# surface.net
KiCad netlist of a schematic drawn in Altium Designer
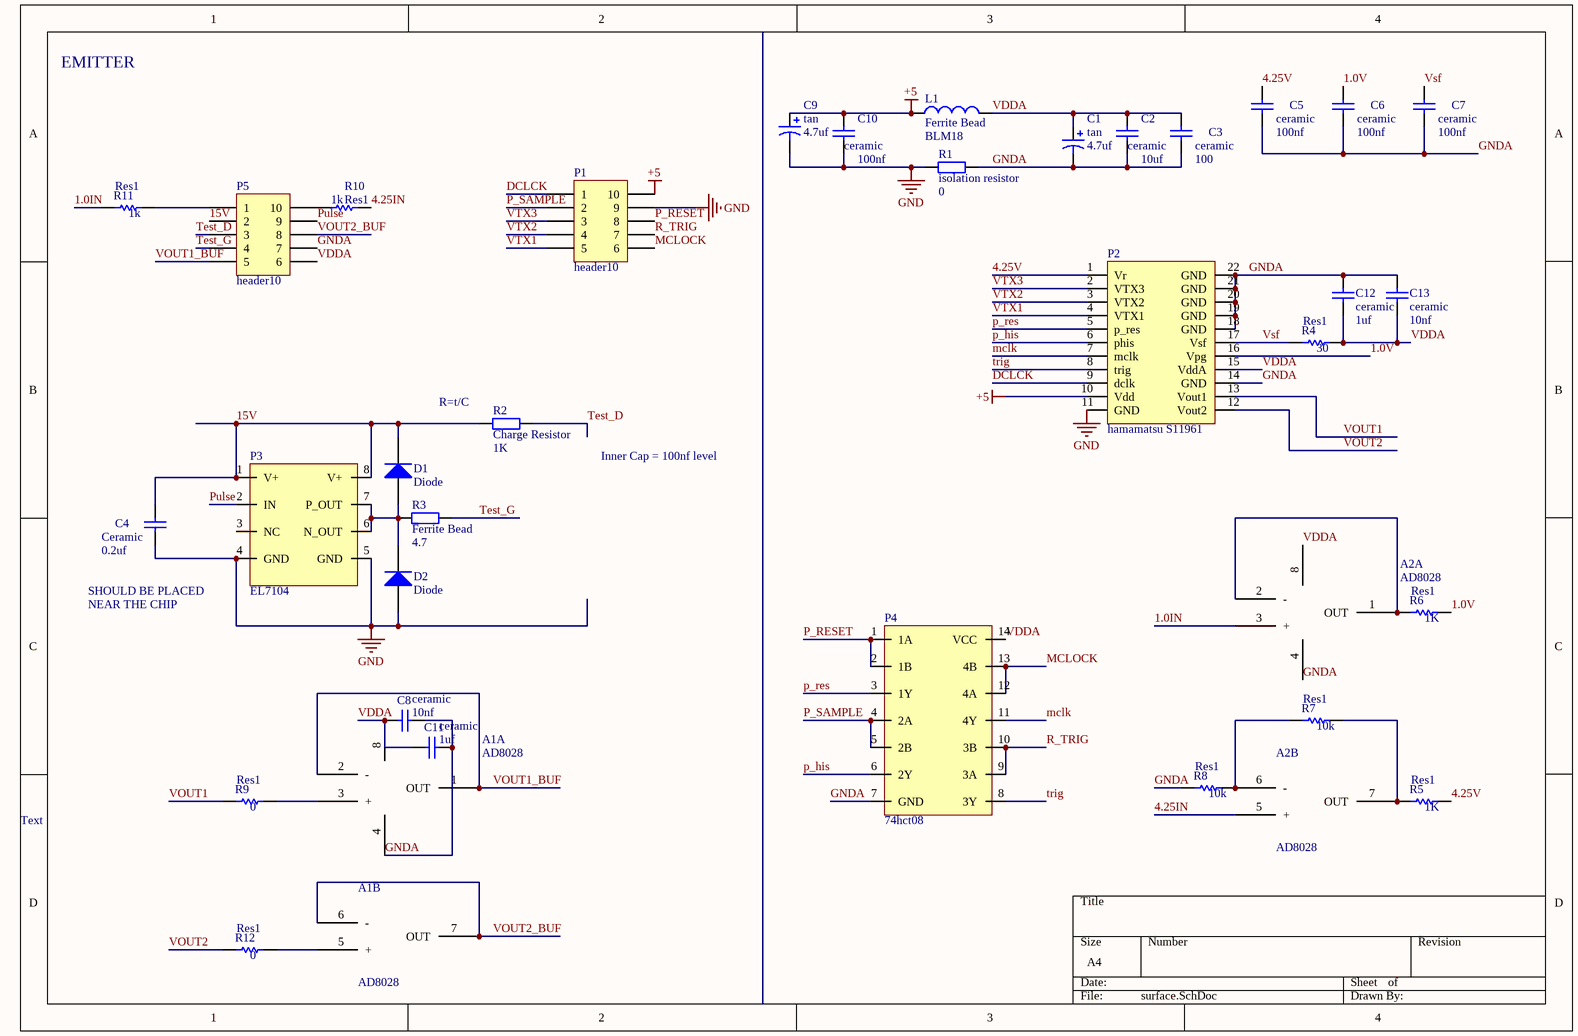
[diagram p0: surface.SchDoc]

(export (version "E")
  (design (tool "Eeschema 10.0.6"))
  (components
    (comp (ref "A1") (value "AD8028") (footprint "so-8") (libsource (lib "jskschemlib") (part "AD8028")))
    (comp (ref "A2") (value "AD8028") (footprint "so-8") (libsource (lib "jskschemlib") (part "AD8028")))
    (comp (ref "C1")
      (value "tan")
      (footprint "C1206+")
      (description "Polarized Capacitor (Surface Mount)")
      (fields (field (name "ALTIUM_VALUE") "4.7uf") (field (name "PUBLISHER") "Altium Limited"))
      (libsource (lib "Miscellaneous Devices") (part "Cap Pol3"))
    )
    (comp (ref "C2")
      (value "ceramic")
      (footprint "J1-0603")
      (description "Capacitor")
      (fields (field (name "ALTIUM_VALUE") "10uf") (field (name "PUBLISHER") "Altium Limited"))
      (libsource (lib "Miscellaneous Devices") (part "Cap"))
    )
    (comp (ref "C3")
      (value "ceramic")
      (footprint "J1-0603")
      (description "Capacitor")
      (fields (field (name "ALTIUM_VALUE") "100") (field (name "PUBLISHER") "Altium Limited"))
      (libsource (lib "Miscellaneous Devices") (part "Cap"))
    )
    (comp (ref "C4")
      (value "Ceramic")
      (footprint "J1-0603")
      (description "Capacitor")
      (fields (field (name "ALTIUM_VALUE") "0.2uf") (field (name "PUBLISHER") "Altium Limited"))
      (libsource (lib "Miscellaneous Devices") (part "Cap"))
    )
    (comp (ref "C5")
      (value "ceramic")
      (footprint "J1-0603")
      (description "Capacitor")
      (fields (field (name "ALTIUM_VALUE") "100nf") (field (name "PUBLISHER") "Altium Limited"))
      (libsource (lib "Miscellaneous Devices") (part "Cap"))
    )
    (comp (ref "C6")
      (value "ceramic")
      (footprint "J1-0603")
      (description "Capacitor")
      (fields (field (name "ALTIUM_VALUE") "100nf") (field (name "PUBLISHER") "Altium Limited"))
      (libsource (lib "Miscellaneous Devices") (part "Cap"))
    )
    (comp (ref "C7")
      (value "ceramic")
      (footprint "J1-0603")
      (description "Capacitor")
      (fields (field (name "ALTIUM_VALUE") "100nf") (field (name "PUBLISHER") "Altium Limited"))
      (libsource (lib "Miscellaneous Devices") (part "Cap"))
    )
    (comp (ref "C8")
      (value "ceramic")
      (footprint "J1-0603")
      (description "Capacitor")
      (fields (field (name "ALTIUM_VALUE") "10nf") (field (name "PUBLISHER") "Altium Limited"))
      (libsource (lib "Miscellaneous Devices") (part "Cap"))
    )
    (comp (ref "C9")
      (value "tan")
      (footprint "C1206+")
      (description "Polarized Capacitor (Surface Mount)")
      (fields (field (name "ALTIUM_VALUE") "4.7uf") (field (name "PUBLISHER") "Altium Limited"))
      (libsource (lib "Miscellaneous Devices") (part "Cap Pol3"))
    )
    (comp (ref "C10")
      (value "ceramic")
      (footprint "J1-0603")
      (description "Capacitor")
      (fields (field (name "ALTIUM_VALUE") "100nf") (field (name "PUBLISHER") "Altium Limited"))
      (libsource (lib "Miscellaneous Devices") (part "Cap"))
    )
    (comp (ref "C11")
      (value "ceramic")
      (footprint "J1-0603")
      (description "Capacitor")
      (fields (field (name "ALTIUM_VALUE") "1uf") (field (name "PUBLISHER") "Altium Limited"))
      (libsource (lib "Miscellaneous Devices") (part "Cap"))
    )
    (comp (ref "C12")
      (value "ceramic")
      (footprint "J1-0603")
      (description "Capacitor")
      (fields (field (name "ALTIUM_VALUE") "1uf") (field (name "PUBLISHER") "Altium Limited"))
      (libsource (lib "Miscellaneous Devices") (part "Cap"))
    )
    (comp (ref "C13")
      (value "ceramic")
      (footprint "J1-0603")
      (description "Capacitor")
      (fields (field (name "ALTIUM_VALUE") "10nf") (field (name "PUBLISHER") "Altium Limited"))
      (libsource (lib "Miscellaneous Devices") (part "Cap"))
    )
    (comp (ref "D1")
      (value "Diode")
      (footprint "DIODE")
      (description "Default Diode")
      (fields (field (name "PUBLISHER") "Altium Limited"))
      (libsource (lib "Miscellaneous Devices") (part "Diode"))
    )
    (comp (ref "D2")
      (value "Diode")
      (footprint "DIODE")
      (description "Default Diode")
      (fields (field (name "PUBLISHER") "Altium Limited"))
      (libsource (lib "Miscellaneous Devices") (part "Diode"))
    )
    (comp (ref "L1")
      (value "Ferrite Bead")
      (footprint "J1-0603")
      (description "Inductor")
      (fields (field (name "ALTIUM_VALUE") "BLM18") (field (name "PUBLISHER") "Altium Limited"))
      (libsource (lib "Miscellaneous Devices") (part "Inductor"))
    )
    (comp (ref "P1")
      (value "header10")
      (footprint "btb10p_f")
      (libsource (lib "jskschemlib") (part "header10"))
    )
    (comp (ref "P2")
      (value "hamamatsu S11961")
      (footprint "s11961")
      (libsource (lib "jskschemlib") (part "S11961"))
    )
    (comp (ref "P3") (value "EL7104") (footprint "so-8") (libsource (lib "jskschemlib") (part "EL7104")))
    (comp (ref "P4") (value "74hct08") (footprint "TSOP14") (libsource (lib "jskschemlib") (part "74alvc08")))
    (comp (ref "P5")
      (value "header10")
      (footprint "btb10p_f")
      (libsource (lib "jskschemlib") (part "header10"))
    )
    (comp (ref "R1")
      (value "isolation resistor")
      (footprint "J1-0603")
      (description "Resistor")
      (fields (field (name "ALTIUM_VALUE") "0") (field (name "PUBLISHER") "Altium Limited"))
      (libsource (lib "Miscellaneous Devices") (part "Res2"))
    )
    (comp (ref "R2")
      (value "Charge Resistor")
      (footprint "2512")
      (description "Resistor")
      (fields (field (name "ALTIUM_VALUE") "1K") (field (name "PUBLISHER") "Altium Limited"))
      (libsource (lib "Miscellaneous Devices") (part "Res2"))
    )
    (comp (ref "R3")
      (value "Ferrite Bead")
      (footprint "0805")
      (description "Resistor")
      (fields (field (name "ALTIUM_VALUE") "4.7") (field (name "PUBLISHER") "Altium Limited"))
      (libsource (lib "Miscellaneous Devices") (part "Res2"))
    )
    (comp (ref "R4")
      (value "Res1")
      (footprint "J1-0603")
      (description "Resistor")
      (fields (field (name "ALTIUM_VALUE") "30") (field (name "PUBLISHER") "Altium Limited"))
      (libsource (lib "Miscellaneous Devices") (part "Res1"))
    )
    (comp (ref "R5")
      (value "Res1")
      (footprint "J1-0603")
      (description "Resistor")
      (fields (field (name "ALTIUM_VALUE") "1K") (field (name "PUBLISHER") "Altium Limited"))
      (libsource (lib "Miscellaneous Devices") (part "Res1"))
    )
    (comp (ref "R6")
      (value "Res1")
      (footprint "J1-0603")
      (description "Resistor")
      (fields (field (name "ALTIUM_VALUE") "1K") (field (name "PUBLISHER") "Altium Limited"))
      (libsource (lib "Miscellaneous Devices") (part "Res1"))
    )
    (comp (ref "R7")
      (value "Res1")
      (footprint "J1-0603")
      (description "Resistor")
      (fields (field (name "ALTIUM_VALUE") "10k") (field (name "PUBLISHER") "Altium Limited"))
      (libsource (lib "Miscellaneous Devices") (part "Res1"))
    )
    (comp (ref "R8")
      (value "Res1")
      (footprint "J1-0603")
      (description "Resistor")
      (fields (field (name "ALTIUM_VALUE") "10k") (field (name "PUBLISHER") "Altium Limited"))
      (libsource (lib "Miscellaneous Devices") (part "Res1"))
    )
    (comp (ref "R9")
      (value "Res1")
      (footprint "J1-0603")
      (description "Resistor")
      (fields (field (name "ALTIUM_VALUE") "0") (field (name "PUBLISHER") "Altium Limited"))
      (libsource (lib "Miscellaneous Devices") (part "Res1"))
    )
    (comp (ref "R10")
      (value "Res1")
      (footprint "J1-0603")
      (description "Resistor")
      (fields (field (name "ALTIUM_VALUE") "1k") (field (name "PUBLISHER") "Altium Limited"))
      (libsource (lib "Miscellaneous Devices") (part "Res1"))
    )
    (comp (ref "R11")
      (value "Res1")
      (footprint "J1-0603")
      (description "Resistor")
      (fields (field (name "ALTIUM_VALUE") "1k") (field (name "PUBLISHER") "Altium Limited"))
      (libsource (lib "Miscellaneous Devices") (part "Res1"))
    )
    (comp (ref "R12")
      (value "Res1")
      (footprint "J1-0603")
      (description "Resistor")
      (fields (field (name "ALTIUM_VALUE") "0") (field (name "PUBLISHER") "Altium Limited"))
      (libsource (lib "Miscellaneous Devices") (part "Res1"))
    )
  )
  (nets
    (net (code "1") (name "+5") (class "Default")
      (node (ref "C10") (pin "2") (pinfunction "2_2") (pintype "passive"))
      (node (ref "C9") (pin "1") (pinfunction "1_1") (pintype "passive"))
      (node (ref "L1") (pin "1") (pinfunction "1_1") (pintype "passive"))
      (node (ref "P1") (pin "10") (pinfunction "10_10") (pintype "passive"))
      (node (ref "P2") (pin "10") (pinfunction "Vdd_10") (pintype "passive"))
    )
    (net (code "2") (name "/1.0IN") (class "Default")
      (node (ref "A2") (pin "3") (pinfunction "+_3") (pintype "passive"))
      (node (ref "R11") (pin "1") (pinfunction "1_1") (pintype "passive"))
    )
    (net (code "3") (name "/1.0V") (class "Default")
      (node (ref "C6") (pin "2") (pinfunction "2_2") (pintype "passive"))
      (node (ref "P2") (pin "16") (pinfunction "Vpg_16") (pintype "passive"))
      (node (ref "R6") (pin "2") (pinfunction "2_2") (pintype "passive"))
    )
    (net (code "4") (name "/4.25IN") (class "Default")
      (node (ref "A2") (pin "5") (pinfunction "+_5") (pintype "passive"))
      (node (ref "R10") (pin "1") (pinfunction "1_1") (pintype "passive"))
    )
    (net (code "5") (name "/4.25V") (class "Default")
      (node (ref "C5") (pin "2") (pinfunction "2_2") (pintype "passive"))
      (node (ref "P2") (pin "1") (pinfunction "Vr_1") (pintype "passive"))
      (node (ref "R5") (pin "2") (pinfunction "2_2") (pintype "passive"))
    )
    (net (code "6") (name "/15V") (class "Default")
      (node (ref "C4") (pin "2") (pinfunction "2_2") (pintype "passive"))
      (node (ref "D1") (pin "2") (pinfunction "K_2") (pintype "passive"))
      (node (ref "P3") (pin "1") (pinfunction "V+_1") (pintype "passive"))
      (node (ref "P3") (pin "8") (pinfunction "V+_8") (pintype "passive"))
      (node (ref "P5") (pin "2") (pinfunction "2_2") (pintype "passive"))
      (node (ref "R2") (pin "1") (pinfunction "1_1") (pintype "passive"))
    )
    (net (code "7") (name "/DCLCK") (class "Default")
      (node (ref "P1") (pin "1") (pinfunction "1_1") (pintype "passive"))
      (node (ref "P2") (pin "9") (pinfunction "dclk_9") (pintype "passive"))
    )
    (net (code "8") (name "/GNDA") (class "Default")
      (node (ref "A1") (pin "4") (pintype "passive"))
      (node (ref "A2") (pin "4") (pintype "passive"))
      (node (ref "C1") (pin "2") (pinfunction "2_2") (pintype "passive"))
      (node (ref "C11") (pin "1") (pinfunction "1_1") (pintype "passive"))
      (node (ref "C12") (pin "2") (pinfunction "2_2") (pintype "passive"))
      (node (ref "C13") (pin "1") (pinfunction "1_1") (pintype "passive"))
      (node (ref "C2") (pin "1") (pinfunction "1_1") (pintype "passive"))
      (node (ref "C3") (pin "1") (pinfunction "1_1") (pintype "passive"))
      (node (ref "C5") (pin "1") (pinfunction "1_1") (pintype "passive"))
      (node (ref "C6") (pin "1") (pinfunction "1_1") (pintype "passive"))
      (node (ref "C7") (pin "1") (pinfunction "1_1") (pintype "passive"))
      (node (ref "C8") (pin "1") (pinfunction "1_1") (pintype "passive"))
      (node (ref "P2") (pin "14") (pinfunction "GND_14") (pintype "passive"))
      (node (ref "P2") (pin "18") (pinfunction "GND_18") (pintype "passive"))
      (node (ref "P2") (pin "19") (pinfunction "GND_19") (pintype "passive"))
      (node (ref "P2") (pin "20") (pinfunction "GND_20") (pintype "passive"))
      (node (ref "P2") (pin "21") (pinfunction "GND_21") (pintype "passive"))
      (node (ref "P2") (pin "22") (pinfunction "GND_22") (pintype "passive"))
      (node (ref "P4") (pin "7") (pinfunction "GND_7") (pintype "passive"))
      (node (ref "P5") (pin "7") (pinfunction "7_7") (pintype "passive"))
      (node (ref "R1") (pin "2") (pinfunction "2_2") (pintype "passive"))
      (node (ref "R8") (pin "1") (pinfunction "1_1") (pintype "passive"))
    )
    (net (code "9") (name "/MCLOCK") (class "Default")
      (node (ref "P1") (pin "6") (pinfunction "6_6") (pintype "passive"))
      (node (ref "P4") (pin "12") (pinfunction "4A_12") (pintype "passive"))
      (node (ref "P4") (pin "13") (pinfunction "4B_13") (pintype "passive"))
    )
    (net (code "10") (name "/P_RESET") (class "Default")
      (node (ref "P1") (pin "8") (pinfunction "8_8") (pintype "passive"))
      (node (ref "P4") (pin "1") (pinfunction "1A_1") (pintype "passive"))
      (node (ref "P4") (pin "2") (pinfunction "1B_2") (pintype "passive"))
    )
    (net (code "11") (name "/P_SAMPLE") (class "Default")
      (node (ref "P1") (pin "2") (pinfunction "2_2") (pintype "passive"))
      (node (ref "P4") (pin "4") (pinfunction "2A_4") (pintype "passive"))
      (node (ref "P4") (pin "5") (pinfunction "2B_5") (pintype "passive"))
    )
    (net (code "12") (name "/Pulse") (class "Default")
      (node (ref "P3") (pin "2") (pinfunction "IN_2") (pintype "passive"))
      (node (ref "P5") (pin "9") (pinfunction "9_9") (pintype "passive"))
    )
    (net (code "13") (name "/R_TRIG") (class "Default")
      (node (ref "P1") (pin "7") (pinfunction "7_7") (pintype "passive"))
      (node (ref "P4") (pin "10") (pinfunction "3B_10") (pintype "passive"))
      (node (ref "P4") (pin "9") (pinfunction "3A_9") (pintype "passive"))
    )
    (net (code "14") (name "/Test_D") (class "Default")
      (node (ref "P5") (pin "3") (pinfunction "3_3") (pintype "passive"))
      (node (ref "R2") (pin "2") (pinfunction "2_2") (pintype "passive"))
    )
    (net (code "15") (name "/Test_G") (class "Default")
      (node (ref "P5") (pin "4") (pinfunction "4_4") (pintype "passive"))
      (node (ref "R3") (pin "2") (pinfunction "2_2") (pintype "passive"))
    )
    (net (code "16") (name "/VDDA") (class "Default")
      (node (ref "A1") (pin "8") (pintype "passive"))
      (node (ref "A2") (pin "8") (pintype "passive"))
      (node (ref "C1") (pin "1") (pinfunction "1_1") (pintype "passive"))
      (node (ref "C11") (pin "2") (pinfunction "2_2") (pintype "passive"))
      (node (ref "C12") (pin "1") (pinfunction "1_1") (pintype "passive"))
      (node (ref "C13") (pin "2") (pinfunction "2_2") (pintype "passive"))
      (node (ref "C2") (pin "2") (pinfunction "2_2") (pintype "passive"))
      (node (ref "C3") (pin "2") (pinfunction "2_2") (pintype "passive"))
      (node (ref "C8") (pin "2") (pinfunction "2_2") (pintype "passive"))
      (node (ref "L1") (pin "2") (pinfunction "2_2") (pintype "passive"))
      (node (ref "P2") (pin "15") (pinfunction "VddA_15") (pintype "passive"))
      (node (ref "P4") (pin "14") (pinfunction "VCC_14") (pintype "passive"))
      (node (ref "P5") (pin "6") (pinfunction "6_6") (pintype "passive"))
      (node (ref "R4") (pin "2") (pinfunction "2_2") (pintype "passive"))
    )
    (net (code "17") (name "/VOUT1") (class "Default")
      (node (ref "P2") (pin "13") (pinfunction "Vout1_13") (pintype "passive"))
      (node (ref "R9") (pin "1") (pinfunction "1_1") (pintype "passive"))
    )
    (net (code "18") (name "/VOUT1_BUF") (class "Default")
      (node (ref "A1") (pin "1") (pinfunction "OUT_1") (pintype "passive"))
      (node (ref "A1") (pin "2") (pinfunction "-_2") (pintype "passive"))
      (node (ref "P5") (pin "5") (pinfunction "5_5") (pintype "passive"))
    )
    (net (code "19") (name "/VOUT2") (class "Default")
      (node (ref "P2") (pin "12") (pinfunction "Vout2_12") (pintype "passive"))
      (node (ref "R12") (pin "1") (pinfunction "1_1") (pintype "passive"))
    )
    (net (code "20") (name "/VOUT2_BUF") (class "Default")
      (node (ref "A1") (pin "6") (pinfunction "-_6") (pintype "passive"))
      (node (ref "A1") (pin "7") (pinfunction "OUT_7") (pintype "passive"))
      (node (ref "P5") (pin "8") (pinfunction "8_8") (pintype "passive"))
    )
    (net (code "21") (name "/VTX1") (class "Default")
      (node (ref "P1") (pin "5") (pinfunction "5_5") (pintype "passive"))
      (node (ref "P2") (pin "4") (pinfunction "VTX1_4") (pintype "passive"))
    )
    (net (code "22") (name "/VTX2") (class "Default")
      (node (ref "P1") (pin "4") (pinfunction "4_4") (pintype "passive"))
      (node (ref "P2") (pin "3") (pinfunction "VTX2_3") (pintype "passive"))
    )
    (net (code "23") (name "/VTX3") (class "Default")
      (node (ref "P1") (pin "3") (pinfunction "3_3") (pintype "passive"))
      (node (ref "P2") (pin "2") (pinfunction "VTX3_2") (pintype "passive"))
    )
    (net (code "24") (name "/Vsf") (class "Default")
      (node (ref "C7") (pin "2") (pinfunction "2_2") (pintype "passive"))
      (node (ref "P2") (pin "17") (pinfunction "Vsf_17") (pintype "passive"))
      (node (ref "R4") (pin "1") (pinfunction "1_1") (pintype "passive"))
    )
    (net (code "25") (name "/mclk") (class "Default")
      (node (ref "P2") (pin "7") (pinfunction "mclk_7") (pintype "passive"))
      (node (ref "P4") (pin "11") (pinfunction "4Y_11") (pintype "passive"))
    )
    (net (code "26") (name "/p_his") (class "Default")
      (node (ref "P2") (pin "6") (pinfunction "phis_6") (pintype "passive"))
      (node (ref "P4") (pin "6") (pinfunction "2Y_6") (pintype "passive"))
    )
    (net (code "27") (name "/p_res") (class "Default")
      (node (ref "P2") (pin "5") (pinfunction "p_res_5") (pintype "passive"))
      (node (ref "P4") (pin "3") (pinfunction "1Y_3") (pintype "passive"))
    )
    (net (code "28") (name "/trig") (class "Default")
      (node (ref "P2") (pin "8") (pinfunction "trig_8") (pintype "passive"))
      (node (ref "P4") (pin "8") (pinfunction "3Y_8") (pintype "passive"))
    )
    (net (code "29") (name "GND") (class "Default")
      (node (ref "C10") (pin "1") (pinfunction "1_1") (pintype "passive"))
      (node (ref "C4") (pin "1") (pinfunction "1_1") (pintype "passive"))
      (node (ref "C9") (pin "2") (pinfunction "2_2") (pintype "passive"))
      (node (ref "D2") (pin "1") (pinfunction "A_1") (pintype "passive"))
      (node (ref "P1") (pin "9") (pinfunction "9_9") (pintype "passive"))
      (node (ref "P2") (pin "11") (pinfunction "GND_11") (pintype "passive"))
      (node (ref "P3") (pin "4") (pinfunction "GND_4") (pintype "passive"))
      (node (ref "P3") (pin "5") (pinfunction "GND_5") (pintype "passive"))
      (node (ref "R1") (pin "1") (pinfunction "1_1") (pintype "passive"))
    )
    (net (code "30") (name "Net-(A1A-+)") (class "Default")
      (node (ref "A1") (pin "3") (pinfunction "+_3") (pintype "passive"))
      (node (ref "R9") (pin "2") (pinfunction "2_2") (pintype "passive"))
    )
    (net (code "31") (name "Net-(A1B-+)") (class "Default")
      (node (ref "A1") (pin "5") (pinfunction "+_5") (pintype "passive"))
      (node (ref "R12") (pin "2") (pinfunction "2_2") (pintype "passive"))
    )
    (net (code "32") (name "Net-(A2A--)") (class "Default")
      (node (ref "A2") (pin "1") (pinfunction "OUT_1") (pintype "passive"))
      (node (ref "A2") (pin "2") (pinfunction "-_2") (pintype "passive"))
      (node (ref "R6") (pin "1") (pinfunction "1_1") (pintype "passive"))
    )
    (net (code "33") (name "Net-(A2B--)") (class "Default")
      (node (ref "A2") (pin "6") (pinfunction "-_6") (pintype "passive"))
      (node (ref "R7") (pin "1") (pinfunction "1_1") (pintype "passive"))
      (node (ref "R8") (pin "2") (pinfunction "2_2") (pintype "passive"))
    )
    (net (code "34") (name "Net-(A2B-OUT)") (class "Default")
      (node (ref "A2") (pin "7") (pinfunction "OUT_7") (pintype "passive"))
      (node (ref "R5") (pin "1") (pinfunction "1_1") (pintype "passive"))
      (node (ref "R7") (pin "2") (pinfunction "2_2") (pintype "passive"))
    )
    (net (code "35") (name "Net-(D1-A)") (class "Default")
      (node (ref "D1") (pin "1") (pinfunction "A_1") (pintype "passive"))
      (node (ref "D2") (pin "2") (pinfunction "K_2") (pintype "passive"))
      (node (ref "P3") (pin "6") (pinfunction "N_OUT_6") (pintype "passive"))
      (node (ref "P3") (pin "7") (pinfunction "P_OUT_7") (pintype "passive"))
      (node (ref "R3") (pin "1") (pinfunction "1_1") (pintype "passive"))
    )
    (net (code "36") (name "Net-(P5-Pad1)") (class "Default")
      (node (ref "P5") (pin "1") (pinfunction "1_1") (pintype "passive"))
      (node (ref "R11") (pin "2") (pinfunction "2_2") (pintype "passive"))
    )
    (net (code "37") (name "Net-(P5-Pad10)") (class "Default")
      (node (ref "P5") (pin "10") (pinfunction "10_10") (pintype "passive"))
      (node (ref "R10") (pin "2") (pinfunction "2_2") (pintype "passive"))
    )
    (net (code "38") (name "unconnected-(P3-NC-Pad3)") (class "Default")
      (node (ref "P3") (pin "3") (pinfunction "NC_3") (pintype "passive"))
    )
  )
)
